# Wifi_Schemati.net
KiCad netlist of a schematic drawn in EAGLE
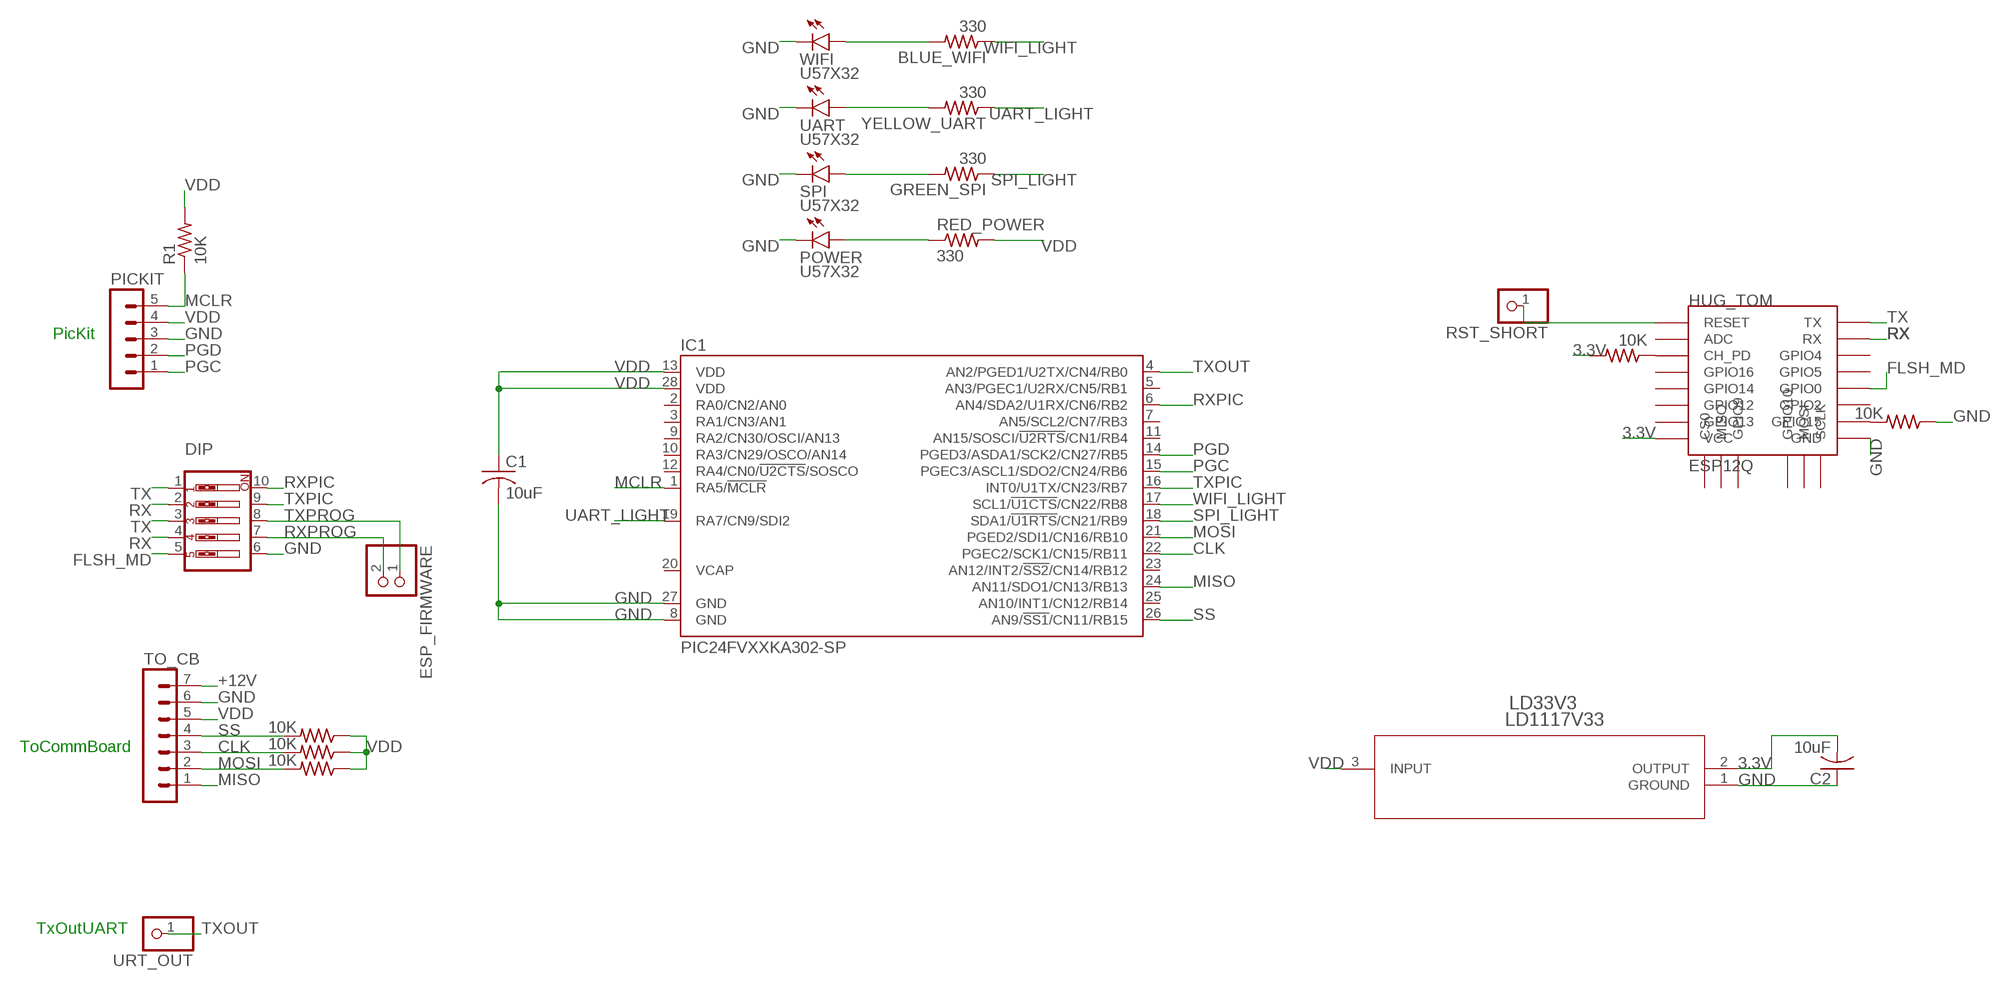
[diagram p0: schematic, sheet 1]

(export (version "E")
  (design (tool "Eeschema 10.0.6"))
  (components
    (comp (ref "BLUE_WIFI")
      (value "330")
      (footprint "eagle-import:0207_7")
      (libsource (lib "eagle-import") (part "R-US_0207/7"))
    )
    (comp (ref "C1")
      (value "10uF")
      (footprint "eagle-import:C025-025X050")
      (libsource (lib "eagle-import") (part "C-US025-025X050"))
    )
    (comp (ref "C2")
      (value "10uF")
      (footprint "eagle-import:C025-025X050")
      (libsource (lib "eagle-import") (part "C-US025-025X050"))
    )
    (comp (ref "DIP")
      (value "SW_DIP-5")
      (footprint "eagle-import:EDG-05")
      (libsource (lib "eagle-import") (part "SW_DIP-5"))
    )
    (comp (ref "ESP_FIRMWARE")
      (value "PINHD-1X2")
      (footprint "eagle-import:1X02")
      (libsource (lib "eagle-import") (part "PINHD-1X2"))
    )
    (comp (ref "GREEN_SPI")
      (value "330")
      (footprint "eagle-import:0207_7")
      (libsource (lib "eagle-import") (part "R-US_0207/7"))
    )
    (comp (ref "HUG_TOM")
      (value "ESP12Q")
      (footprint "eagle-import:ESP12Q")
      (fields (field (name "SPICEPREFIX") "X"))
      (libsource (lib "eagle-import") (part "ESP12Q"))
    )
    (comp (ref "IC1")
      (value "PIC24FVXXKA302-SP")
      (footprint "eagle-import:DIL28-3")
      (libsource (lib "eagle-import") (part "PIC24FVXXKA302-SP"))
    )
    (comp (ref "LD33V3")
      (value "LD1117V33")
      (footprint "eagle-import:TO-220")
      (libsource (lib "eagle-import") (part "LD1117V33"))
    )
    (comp (ref "PICKIT")
      (value "MA05-1")
      (footprint "eagle-import:MA05-1")
      (libsource (lib "eagle-import") (part "MA05-1"))
    )
    (comp (ref "POWER")
      (value "U57X32")
      (footprint "eagle-import:U57X32")
      (libsource (lib "eagle-import") (part "U57X32"))
    )
    (comp (ref "R1")
      (value "10K")
      (footprint "eagle-import:0207_7")
      (libsource (lib "eagle-import") (part "R-US_0207/7"))
    )
    (comp (ref "R2")
      (value "10K")
      (footprint "eagle-import:0207_7")
      (libsource (lib "eagle-import") (part "R-US_0207/7"))
    )
    (comp (ref "R3")
      (value "10K")
      (footprint "eagle-import:0207_7")
      (libsource (lib "eagle-import") (part "R-US_0207/7"))
    )
    (comp (ref "R4")
      (value "10K")
      (footprint "eagle-import:0207_7")
      (libsource (lib "eagle-import") (part "R-US_0207/7"))
    )
    (comp (ref "R5")
      (value "10K")
      (footprint "eagle-import:0207_7")
      (libsource (lib "eagle-import") (part "R-US_0207/7"))
    )
    (comp (ref "R6")
      (value "10K")
      (footprint "eagle-import:0207_7")
      (libsource (lib "eagle-import") (part "R-US_0207/7"))
    )
    (comp (ref "RED_POWER")
      (value "330")
      (footprint "eagle-import:0207_7")
      (libsource (lib "eagle-import") (part "R-US_0207/7"))
    )
    (comp (ref "RST_SHORT")
      (value "PINHD-1X1")
      (footprint "eagle-import:1X01")
      (libsource (lib "eagle-import") (part "PINHD-1X1"))
    )
    (comp (ref "SPI")
      (value "U57X32")
      (footprint "eagle-import:U57X32")
      (libsource (lib "eagle-import") (part "U57X32"))
    )
    (comp (ref "TO_CB")
      (value "MA07-1")
      (footprint "eagle-import:MA07-1")
      (libsource (lib "eagle-import") (part "MA07-1"))
    )
    (comp (ref "UART")
      (value "U57X32")
      (footprint "eagle-import:U57X32")
      (libsource (lib "eagle-import") (part "U57X32"))
    )
    (comp (ref "URT_OUT")
      (value "PINHD-1X1")
      (footprint "eagle-import:1X01")
      (libsource (lib "eagle-import") (part "PINHD-1X1"))
    )
    (comp (ref "WIFI")
      (value "U57X32")
      (footprint "eagle-import:U57X32")
      (libsource (lib "eagle-import") (part "U57X32"))
    )
    (comp (ref "YELLOW_UART")
      (value "330")
      (footprint "eagle-import:0207_7")
      (libsource (lib "eagle-import") (part "R-US_0207/7"))
    )
  )
  (nets
    (net (code "1") (name "/+12V") (class "Default")
      (node (ref "TO_CB") (pin "7") (pinfunction "7_7") (pintype "passive"))
    )
    (net (code "2") (name "/3.3V") (class "Default")
      (node (ref "C2") (pin "2") (pinfunction "2_2") (pintype "passive"))
      (node (ref "HUG_TOM") (pin "VCC") (pinfunction "VCC_VCC") (pintype "bidirectional"))
      (node (ref "LD33V3") (pin "2") (pinfunction "OUTPUT_2") (pintype "passive"))
      (node (ref "R6") (pin "2") (pinfunction "2_2") (pintype "passive"))
    )
    (net (code "3") (name "/CLK") (class "Default")
      (node (ref "IC1") (pin "22") (pinfunction "PGEC2/SCK1/CN15/RB11_22") (pintype "bidirectional"))
      (node (ref "R3") (pin "2") (pinfunction "2_2") (pintype "passive"))
      (node (ref "TO_CB") (pin "3") (pinfunction "3_3") (pintype "passive"))
    )
    (net (code "4") (name "/FLSH_MD") (class "Default")
      (node (ref "DIP") (pin "5") (pinfunction "5_5") (pintype "passive"))
      (node (ref "HUG_TOM") (pin "GPIO0") (pinfunction "GPIO0_GPIO0") (pintype "bidirectional"))
    )
    (net (code "5") (name "/GND") (class "Default")
      (node (ref "C1") (pin "2") (pinfunction "2_2") (pintype "passive"))
      (node (ref "C2") (pin "1") (pinfunction "1_1") (pintype "passive"))
      (node (ref "DIP") (pin "6") (pinfunction "6_6") (pintype "passive"))
      (node (ref "HUG_TOM") (pin "GND") (pinfunction "GND_GND") (pintype "bidirectional"))
      (node (ref "IC1") (pin "27") (pinfunction "GND_27") (pintype "power_in"))
      (node (ref "IC1") (pin "8") (pinfunction "GND_8") (pintype "power_in"))
      (node (ref "LD33V3") (pin "1") (pinfunction "GROUND_1") (pintype "passive"))
      (node (ref "PICKIT") (pin "3") (pinfunction "3_3") (pintype "passive"))
      (node (ref "POWER") (pin "K") (pinfunction "C_K") (pintype "passive"))
      (node (ref "R2") (pin "1") (pinfunction "1_1") (pintype "passive"))
      (node (ref "SPI") (pin "K") (pinfunction "C_K") (pintype "passive"))
      (node (ref "TO_CB") (pin "6") (pinfunction "6_6") (pintype "passive"))
      (node (ref "UART") (pin "K") (pinfunction "C_K") (pintype "passive"))
      (node (ref "WIFI") (pin "K") (pinfunction "C_K") (pintype "passive"))
    )
    (net (code "6") (name "/MCLR") (class "Default")
      (node (ref "IC1") (pin "1") (pinfunction "RA5/~{MCLR}_1") (pintype "bidirectional"))
      (node (ref "PICKIT") (pin "5") (pinfunction "5_5") (pintype "passive"))
      (node (ref "R1") (pin "1") (pinfunction "1_1") (pintype "passive"))
    )
    (net (code "7") (name "/MISO") (class "Default")
      (node (ref "IC1") (pin "24") (pinfunction "AN11/SDO1/CN13/RB13_24") (pintype "bidirectional"))
      (node (ref "TO_CB") (pin "1") (pinfunction "1_1") (pintype "passive"))
    )
    (net (code "8") (name "/MOSI") (class "Default")
      (node (ref "IC1") (pin "21") (pinfunction "PGED2/SDI1/CN16/RB10_21") (pintype "bidirectional"))
      (node (ref "R4") (pin "2") (pinfunction "2_2") (pintype "passive"))
      (node (ref "TO_CB") (pin "2") (pinfunction "2_2") (pintype "passive"))
    )
    (net (code "9") (name "/PGC") (class "Default")
      (node (ref "IC1") (pin "15") (pinfunction "PGEC3/ASCL1/SDO2/CN24/RB6_15") (pintype "bidirectional"))
      (node (ref "PICKIT") (pin "1") (pinfunction "1_1") (pintype "passive"))
    )
    (net (code "10") (name "/PGD") (class "Default")
      (node (ref "IC1") (pin "14") (pinfunction "PGED3/ASDA1/SCK2/CN27/RB5_14") (pintype "bidirectional"))
      (node (ref "PICKIT") (pin "2") (pinfunction "2_2") (pintype "passive"))
    )
    (net (code "11") (name "/RX") (class "Default")
      (node (ref "DIP") (pin "2") (pinfunction "2_2") (pintype "passive"))
      (node (ref "DIP") (pin "4") (pinfunction "4_4") (pintype "passive"))
      (node (ref "HUG_TOM") (pin "RX") (pinfunction "RX_RX") (pintype "bidirectional"))
    )
    (net (code "12") (name "/RXPIC") (class "Default")
      (node (ref "DIP") (pin "10") (pinfunction "10_10") (pintype "passive"))
      (node (ref "IC1") (pin "6") (pinfunction "AN4/SDA2/U1RX/CN6/RB2_6") (pintype "bidirectional"))
    )
    (net (code "13") (name "/RXPROG") (class "Default")
      (node (ref "DIP") (pin "7") (pinfunction "7_7") (pintype "passive"))
      (node (ref "ESP_FIRMWARE") (pin "2") (pinfunction "2_2") (pintype "passive"))
    )
    (net (code "14") (name "/SPI_LIGHT") (class "Default")
      (node (ref "GREEN_SPI") (pin "1") (pinfunction "1_1") (pintype "passive"))
      (node (ref "IC1") (pin "18") (pinfunction "SDA1/~{U1RTS}/CN21/RB9_18") (pintype "bidirectional"))
    )
    (net (code "15") (name "/SS") (class "Default")
      (node (ref "IC1") (pin "26") (pinfunction "AN9/~{SS1}/CN11/RB15_26") (pintype "bidirectional"))
      (node (ref "R5") (pin "2") (pinfunction "2_2") (pintype "passive"))
      (node (ref "TO_CB") (pin "4") (pinfunction "4_4") (pintype "passive"))
    )
    (net (code "16") (name "/TX") (class "Default")
      (node (ref "DIP") (pin "1") (pinfunction "1_1") (pintype "passive"))
      (node (ref "DIP") (pin "3") (pinfunction "3_3") (pintype "passive"))
      (node (ref "HUG_TOM") (pin "TX") (pinfunction "TX_TX") (pintype "bidirectional"))
    )
    (net (code "17") (name "/TXOUT") (class "Default")
      (node (ref "IC1") (pin "4") (pinfunction "AN2/PGED1/U2TX/CN4/RB0_4") (pintype "bidirectional"))
      (node (ref "URT_OUT") (pin "1") (pinfunction "1_1") (pintype "passive"))
    )
    (net (code "18") (name "/TXPIC") (class "Default")
      (node (ref "DIP") (pin "9") (pinfunction "9_9") (pintype "passive"))
      (node (ref "IC1") (pin "16") (pinfunction "INT0/U1TX/CN23/RB7_16") (pintype "bidirectional"))
    )
    (net (code "19") (name "/TXPROG") (class "Default")
      (node (ref "DIP") (pin "8") (pinfunction "8_8") (pintype "passive"))
      (node (ref "ESP_FIRMWARE") (pin "1") (pinfunction "1_1") (pintype "passive"))
    )
    (net (code "20") (name "/UART_LIGHT") (class "Default")
      (node (ref "IC1") (pin "19") (pinfunction "RA7/CN9/SDI2_19") (pintype "bidirectional"))
      (node (ref "YELLOW_UART") (pin "1") (pinfunction "1_1") (pintype "passive"))
    )
    (net (code "21") (name "/VDD") (class "Default")
      (node (ref "C1") (pin "1") (pinfunction "1_1") (pintype "passive"))
      (node (ref "IC1") (pin "13") (pinfunction "VDD_13") (pintype "power_in"))
      (node (ref "IC1") (pin "28") (pinfunction "VDD_28") (pintype "power_in"))
      (node (ref "LD33V3") (pin "3") (pinfunction "INPUT_3") (pintype "passive"))
      (node (ref "PICKIT") (pin "4") (pinfunction "4_4") (pintype "passive"))
      (node (ref "R1") (pin "2") (pinfunction "2_2") (pintype "passive"))
      (node (ref "R3") (pin "1") (pinfunction "1_1") (pintype "passive"))
      (node (ref "R4") (pin "1") (pinfunction "1_1") (pintype "passive"))
      (node (ref "R5") (pin "1") (pinfunction "1_1") (pintype "passive"))
      (node (ref "RED_POWER") (pin "2") (pinfunction "2_2") (pintype "passive"))
      (node (ref "TO_CB") (pin "5") (pinfunction "5_5") (pintype "passive"))
    )
    (net (code "22") (name "/WIFI_LIGHT") (class "Default")
      (node (ref "BLUE_WIFI") (pin "1") (pinfunction "1_1") (pintype "passive"))
      (node (ref "IC1") (pin "17") (pinfunction "SCL1/~{U1CTS}/CN22/RB8_17") (pintype "bidirectional"))
    )
    (net (code "23") (name "Net-(BLUE_WIFI-Pad2)") (class "Default")
      (node (ref "BLUE_WIFI") (pin "2") (pinfunction "2_2") (pintype "passive"))
      (node (ref "WIFI") (pin "A") (pinfunction "A_A") (pintype "passive"))
    )
    (net (code "24") (name "Net-(GREEN_SPI-Pad2)") (class "Default")
      (node (ref "GREEN_SPI") (pin "2") (pinfunction "2_2") (pintype "passive"))
      (node (ref "SPI") (pin "A") (pinfunction "A_A") (pintype "passive"))
    )
    (net (code "25") (name "Net-(HUG_TOM-PadCH_PD)") (class "Default")
      (node (ref "HUG_TOM") (pin "CH_PD") (pinfunction "CH_PD_CH_PD") (pintype "bidirectional"))
      (node (ref "R6") (pin "1") (pinfunction "1_1") (pintype "passive"))
    )
    (net (code "26") (name "Net-(HUG_TOM-PadGPIO15)") (class "Default")
      (node (ref "HUG_TOM") (pin "GPIO15") (pinfunction "GPIO15_GPIO15") (pintype "bidirectional"))
      (node (ref "R2") (pin "2") (pinfunction "2_2") (pintype "passive"))
    )
    (net (code "27") (name "Net-(HUG_TOM-PadRESET)") (class "Default")
      (node (ref "HUG_TOM") (pin "RESET") (pinfunction "RESET_RESET") (pintype "bidirectional"))
      (node (ref "RST_SHORT") (pin "1") (pinfunction "1_1") (pintype "passive"))
    )
    (net (code "28") (name "Net-(POWER-PadA)") (class "Default")
      (node (ref "POWER") (pin "A") (pinfunction "A_A") (pintype "passive"))
      (node (ref "RED_POWER") (pin "1") (pinfunction "1_1") (pintype "passive"))
    )
    (net (code "29") (name "Net-(UART-PadA)") (class "Default")
      (node (ref "UART") (pin "A") (pinfunction "A_A") (pintype "passive"))
      (node (ref "YELLOW_UART") (pin "2") (pinfunction "2_2") (pintype "passive"))
    )
    (net (code "30") (name "unconnected-(HUG_TOM-PadADC)") (class "Default")
      (node (ref "HUG_TOM") (pin "ADC") (pinfunction "ADC_ADC") (pintype "bidirectional"))
    )
    (net (code "31") (name "unconnected-(HUG_TOM-PadCS0)") (class "Default")
      (node (ref "HUG_TOM") (pin "CS0") (pinfunction "CS0_CS0") (pintype "bidirectional"))
    )
    (net (code "32") (name "unconnected-(HUG_TOM-PadGPIO2)") (class "Default")
      (node (ref "HUG_TOM") (pin "GPIO2") (pinfunction "GPIO2_GPIO2") (pintype "bidirectional"))
    )
    (net (code "33") (name "unconnected-(HUG_TOM-PadGPIO4)") (class "Default")
      (node (ref "HUG_TOM") (pin "GPIO4") (pinfunction "GPIO4_GPIO4") (pintype "bidirectional"))
    )
    (net (code "34") (name "unconnected-(HUG_TOM-PadGPIO5)") (class "Default")
      (node (ref "HUG_TOM") (pin "GPIO5") (pinfunction "GPIO5_GPIO5") (pintype "bidirectional"))
    )
    (net (code "35") (name "unconnected-(HUG_TOM-PadGPIO9)") (class "Default")
      (node (ref "HUG_TOM") (pin "GPIO9") (pinfunction "GPIO9_GPIO9") (pintype "bidirectional"))
    )
    (net (code "36") (name "unconnected-(HUG_TOM-PadGPIO10)") (class "Default")
      (node (ref "HUG_TOM") (pin "GPIO10") (pinfunction "GPIO10_GPIO10") (pintype "bidirectional"))
    )
    (net (code "37") (name "unconnected-(HUG_TOM-PadGPIO12)") (class "Default")
      (node (ref "HUG_TOM") (pin "GPIO12") (pinfunction "GPIO12_GPIO12") (pintype "bidirectional"))
    )
    (net (code "38") (name "unconnected-(HUG_TOM-PadGPIO13)") (class "Default")
      (node (ref "HUG_TOM") (pin "GPIO13") (pinfunction "GPIO13_GPIO13") (pintype "bidirectional"))
    )
    (net (code "39") (name "unconnected-(HUG_TOM-PadGPIO14)") (class "Default")
      (node (ref "HUG_TOM") (pin "GPIO14") (pinfunction "GPIO14_GPIO14") (pintype "bidirectional"))
    )
    (net (code "40") (name "unconnected-(HUG_TOM-PadGPIO16)") (class "Default")
      (node (ref "HUG_TOM") (pin "GPIO16") (pinfunction "GPIO16_GPIO16") (pintype "bidirectional"))
    )
    (net (code "41") (name "unconnected-(HUG_TOM-PadMISO)") (class "Default")
      (node (ref "HUG_TOM") (pin "MISO") (pinfunction "MISO_MISO") (pintype "bidirectional"))
    )
    (net (code "42") (name "unconnected-(HUG_TOM-PadMOSI)") (class "Default")
      (node (ref "HUG_TOM") (pin "MOSI") (pinfunction "MOSI_MOSI") (pintype "bidirectional"))
    )
    (net (code "43") (name "unconnected-(HUG_TOM-PadSCLK)") (class "Default")
      (node (ref "HUG_TOM") (pin "SCLK") (pinfunction "SCLK_SCLK") (pintype "bidirectional"))
    )
    (net (code "44") (name "unconnected-(IC1-AN3{slash}PGEC1{slash}U2RX{slash}CN5{slash}RB1-Pad5)") (class "Default")
      (node (ref "IC1") (pin "5") (pinfunction "AN3/PGEC1/U2RX/CN5/RB1_5") (pintype "bidirectional"))
    )
    (net (code "45") (name "unconnected-(IC1-AN5{slash}SCL2{slash}CN7{slash}RB3-Pad7)") (class "Default")
      (node (ref "IC1") (pin "7") (pinfunction "AN5/SCL2/CN7/RB3_7") (pintype "bidirectional"))
    )
    (net (code "46") (name "unconnected-(IC1-AN10{slash}INT1{slash}CN12{slash}RB14-Pad25)") (class "Default")
      (node (ref "IC1") (pin "25") (pinfunction "AN10/INT1/CN12/RB14_25") (pintype "bidirectional"))
    )
    (net (code "47") (name "unconnected-(IC1-AN12{slash}INT2{slash}~{SS2}{slash}CN14{slash}RB12-Pad23)") (class "Default")
      (node (ref "IC1") (pin "23") (pinfunction "AN12/INT2/~{SS2}/CN14/RB12_23") (pintype "bidirectional"))
    )
    (net (code "48") (name "unconnected-(IC1-AN15{slash}SOSCI{slash}~{U2RTS}{slash}CN1{slash}RB4-Pad11)") (class "Default")
      (node (ref "IC1") (pin "11") (pinfunction "AN15/SOSCI/~{U2RTS}/CN1/RB4_11") (pintype "bidirectional"))
    )
    (net (code "49") (name "unconnected-(IC1-RA0{slash}CN2{slash}AN0-Pad2)") (class "Default")
      (node (ref "IC1") (pin "2") (pinfunction "RA0/CN2/AN0_2") (pintype "bidirectional"))
    )
    (net (code "50") (name "unconnected-(IC1-RA1{slash}CN3{slash}AN1-Pad3)") (class "Default")
      (node (ref "IC1") (pin "3") (pinfunction "RA1/CN3/AN1_3") (pintype "bidirectional"))
    )
    (net (code "51") (name "unconnected-(IC1-RA2{slash}CN30{slash}OSCI{slash}AN13-Pad9)") (class "Default")
      (node (ref "IC1") (pin "9") (pinfunction "RA2/CN30/OSCI/AN13_9") (pintype "bidirectional"))
    )
    (net (code "52") (name "unconnected-(IC1-RA3{slash}CN29{slash}OSCO{slash}AN14-Pad10)") (class "Default")
      (node (ref "IC1") (pin "10") (pinfunction "RA3/CN29/OSCO/AN14_10") (pintype "bidirectional"))
    )
    (net (code "53") (name "unconnected-(IC1-RA4{slash}CN0{slash}~{U2CTS}{slash}SOSCO-Pad12)") (class "Default")
      (node (ref "IC1") (pin "12") (pinfunction "RA4/CN0/~{U2CTS}/SOSCO_12") (pintype "bidirectional"))
    )
    (net (code "54") (name "unconnected-(IC1-VCAP-Pad20)") (class "Default")
      (node (ref "IC1") (pin "20") (pinfunction "VCAP_20") (pintype "passive"))
    )
  )
)
